# DASH_itr5_v3_labelled.net
KiCad netlist of a schematic drawn in EAGLE
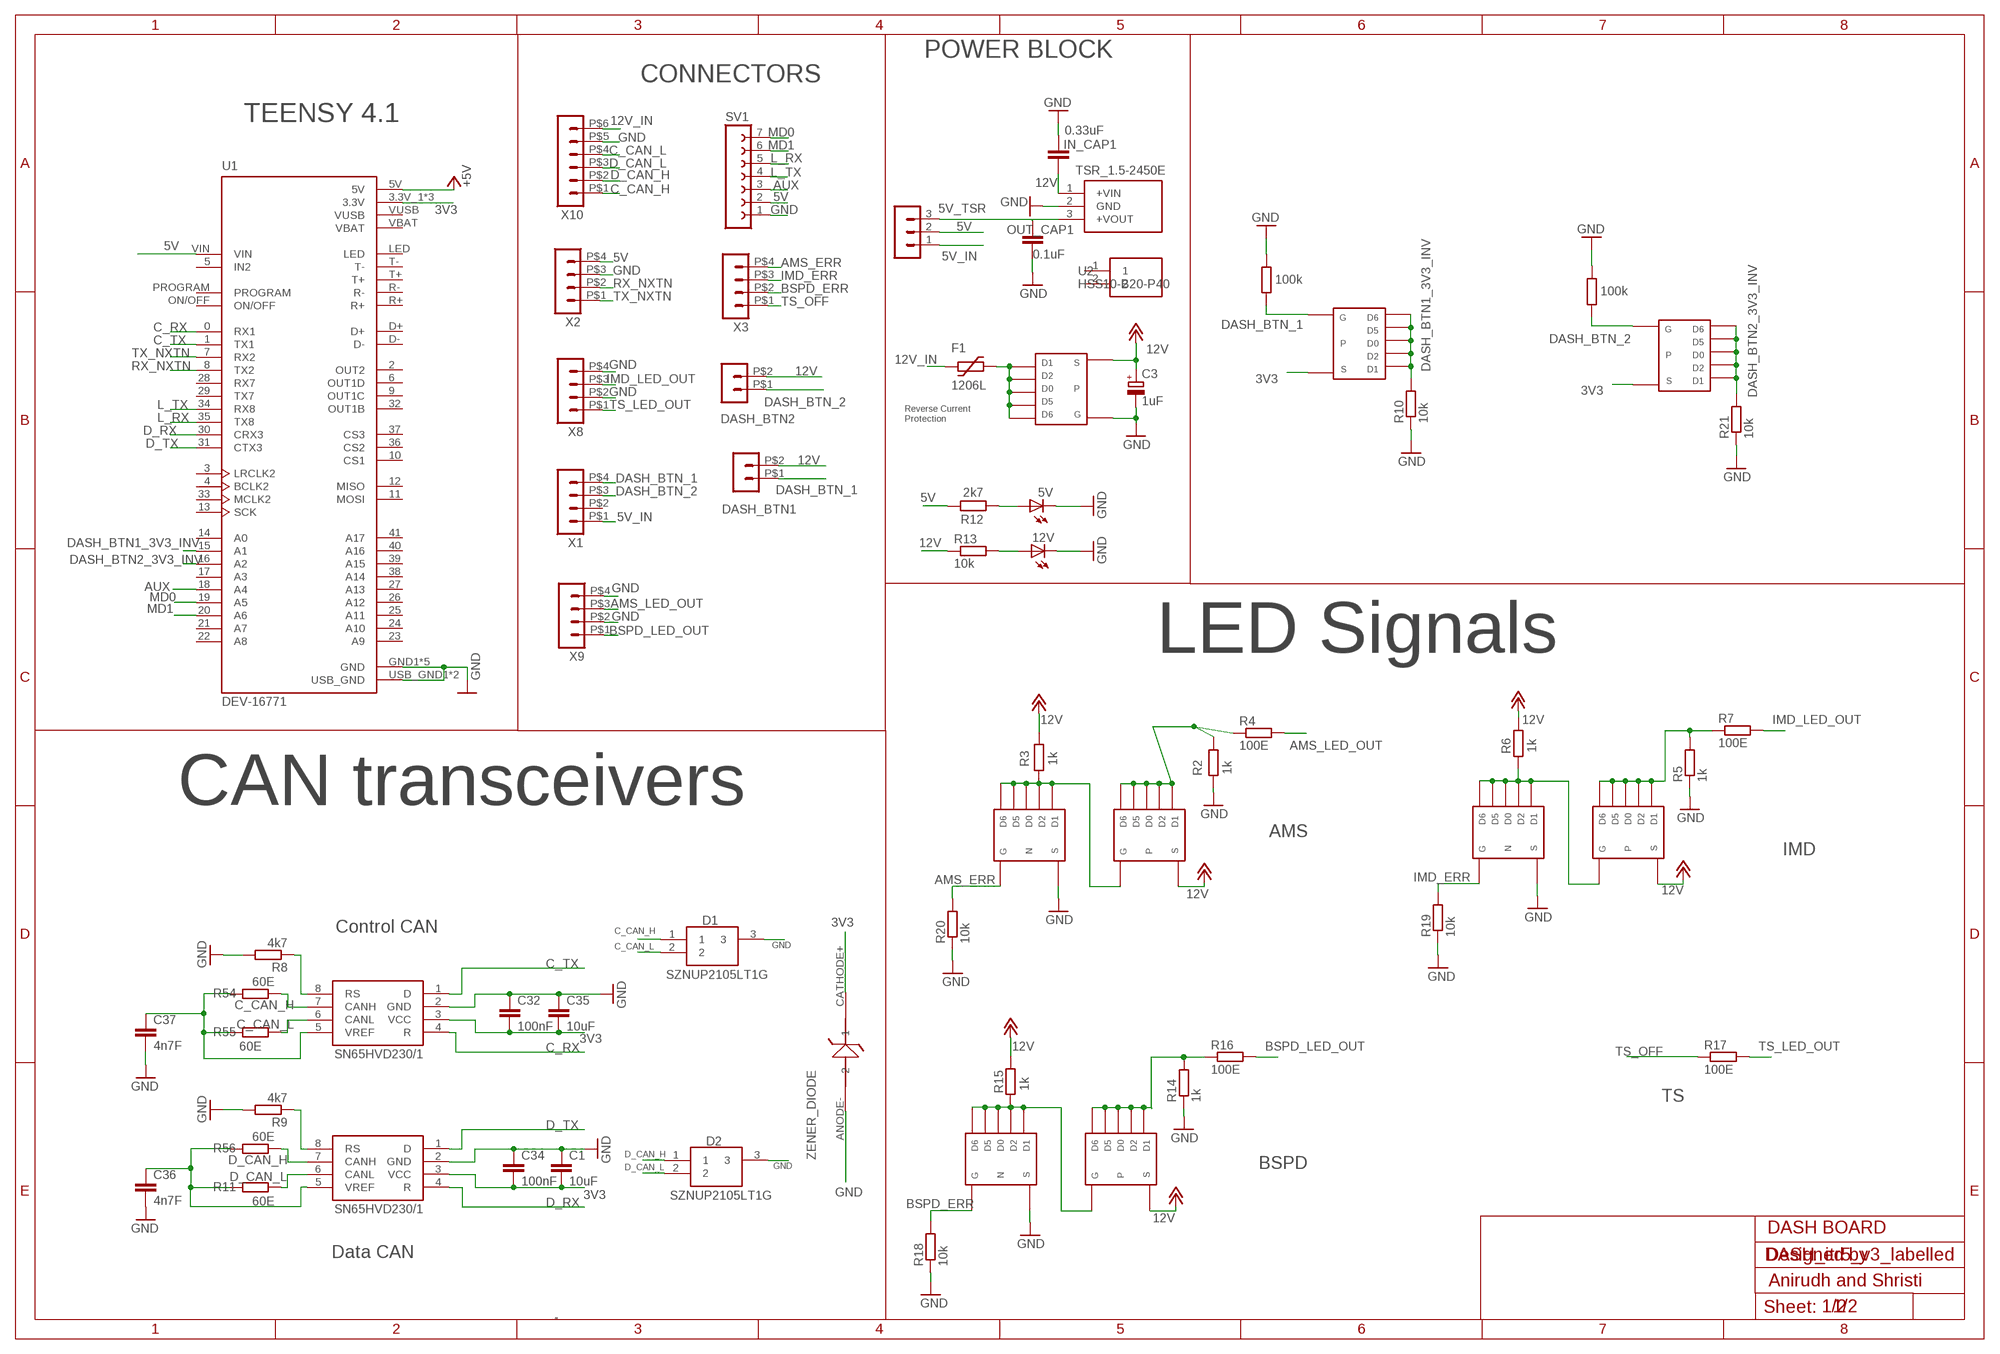
[diagram p0: schematic, sheet 1]
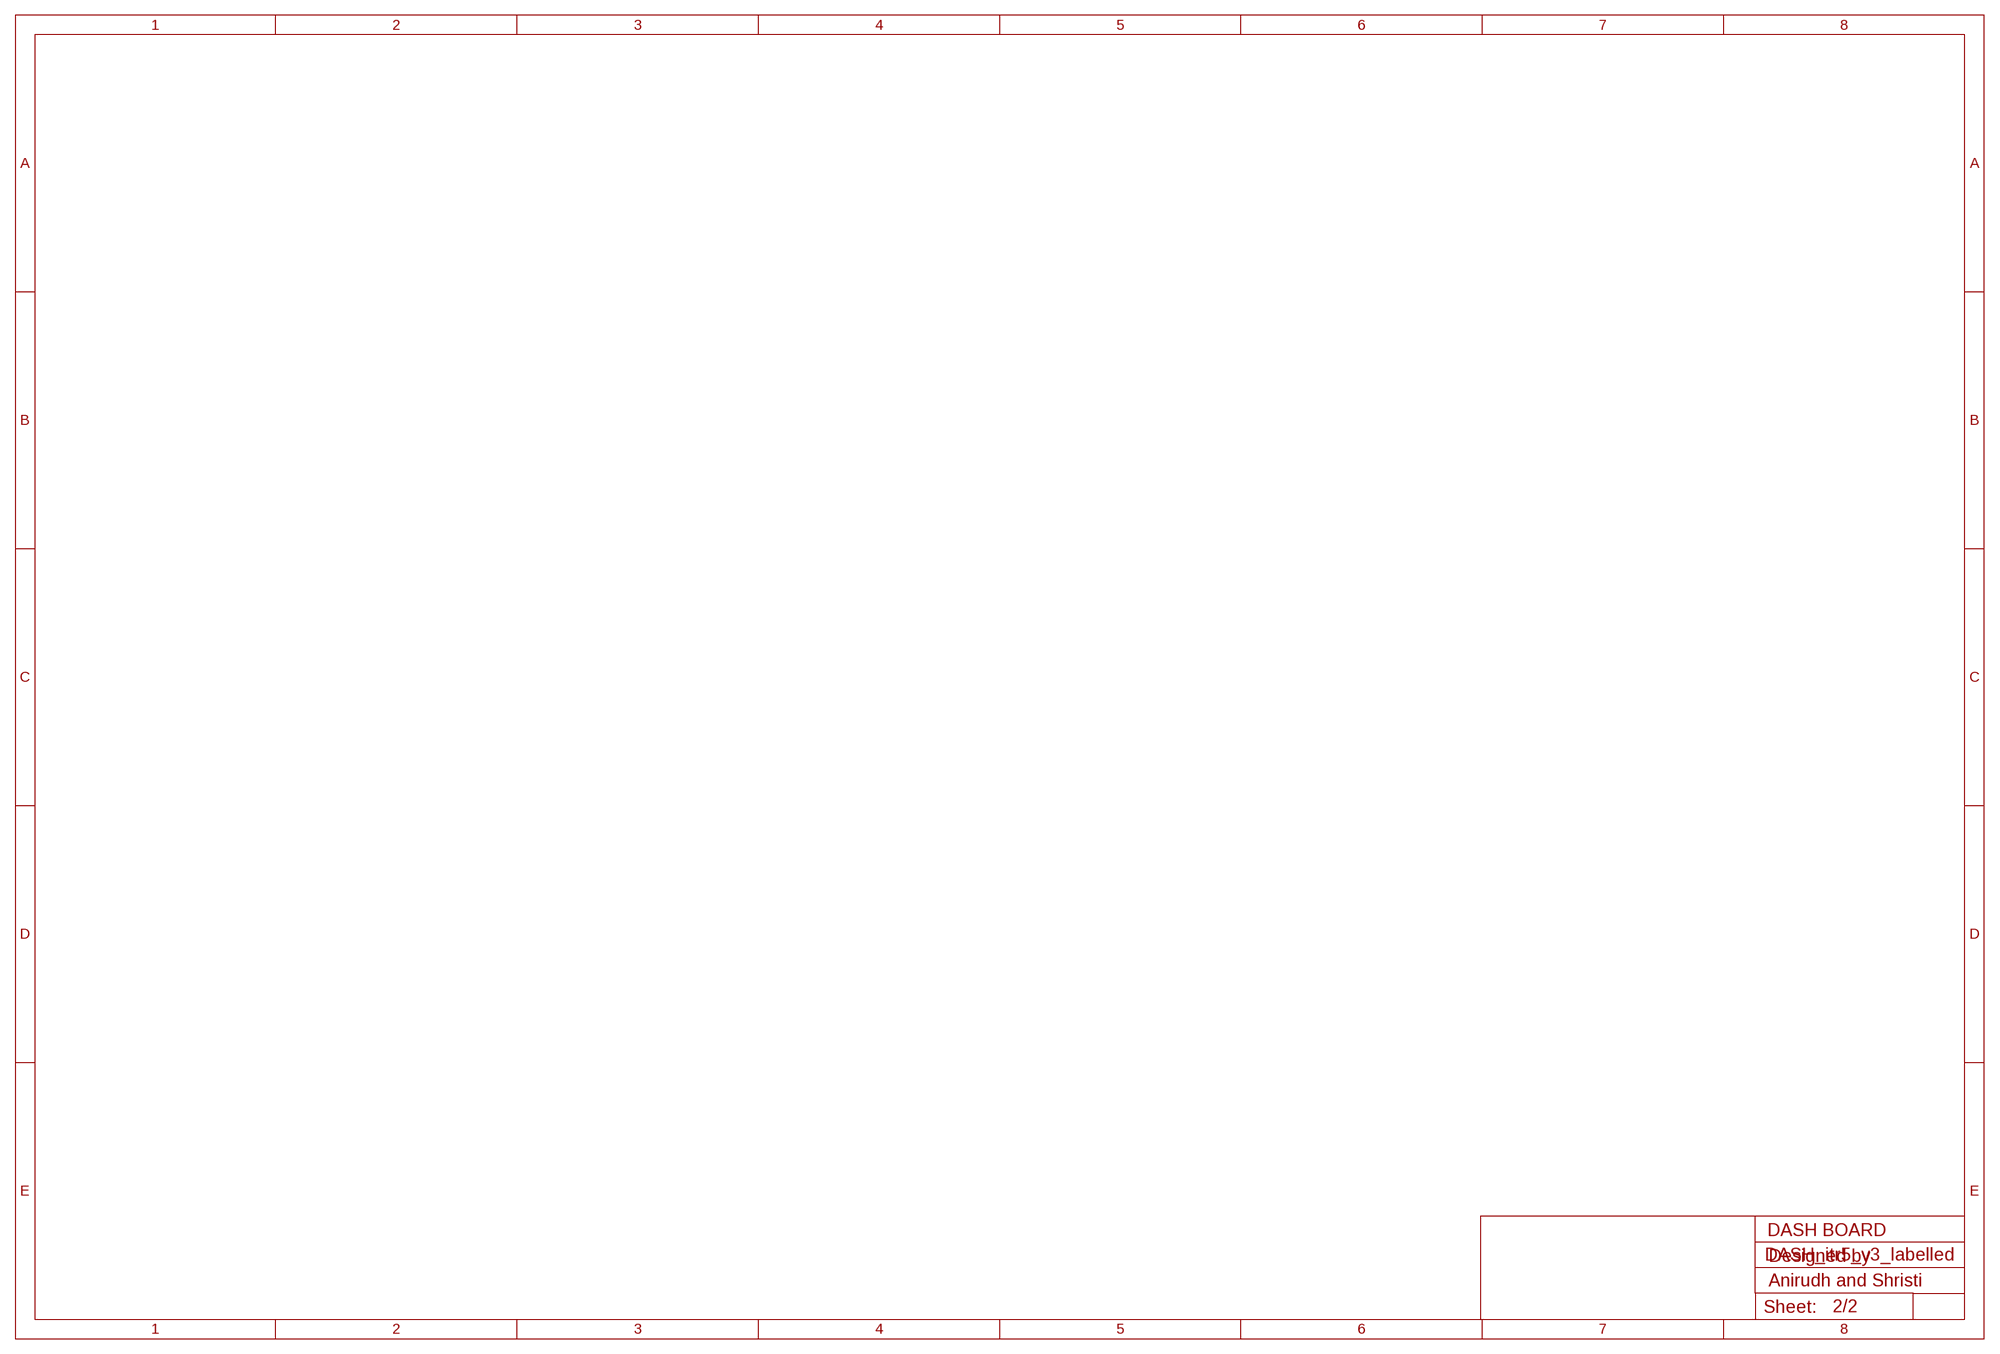
[diagram p1: schematic, sheet 2]

(export (version "E")
  (design (tool "Eeschema 10.0.6"))
  (components
    (comp (ref "5V")
      (value "LED-FKIT-1206")
      (footprint "eagle-import:FKIT-LED-1206")
      (libsource (lib "eagle-import") (part "LED-FKIT-1206"))
    )
    (comp (ref "12V")
      (value "LED-FKIT-1206")
      (footprint "eagle-import:FKIT-LED-1206")
      (libsource (lib "eagle-import") (part "LED-FKIT-1206"))
    )
    (comp (ref "C1")
      (value "10uF")
      (footprint "eagle-import:C0805")
      (libsource (lib "eagle-import") (part "C-EUC0805"))
    )
    (comp (ref "C3")
      (value "1uF")
      (footprint "eagle-import:E2,5-6")
      (libsource (lib "eagle-import") (part "CPOL-EUE2.5-6"))
    )
    (comp (ref "C32")
      (value "100nF")
      (footprint "eagle-import:C0805")
      (libsource (lib "eagle-import") (part "C-EUC0805"))
    )
    (comp (ref "C34")
      (value "100nF")
      (footprint "eagle-import:C0805")
      (libsource (lib "eagle-import") (part "C-EUC0805"))
    )
    (comp (ref "C35")
      (value "10uF")
      (footprint "eagle-import:C0805")
      (libsource (lib "eagle-import") (part "C-EUC0805"))
    )
    (comp (ref "C36")
      (value "4n7F")
      (footprint "eagle-import:C0805")
      (libsource (lib "eagle-import") (part "C-EUC0805"))
    )
    (comp (ref "C37")
      (value "4n7F")
      (footprint "eagle-import:C0805")
      (libsource (lib "eagle-import") (part "C-EUC0805"))
    )
    (comp (ref "D1")
      (value "SZNUP2105LT1G")
      (footprint "eagle-import:SOT96P237X111-3N")
      (fields (field (name "MOUSER_PART_NUMBER") "863-SZNUP2105LT1G"))
      (libsource (lib "eagle-import") (part "SZNUP2105LT1G"))
    )
    (comp (ref "D2")
      (value "SZNUP2105LT1G")
      (footprint "eagle-import:SOT96P237X111-3N")
      (fields (field (name "MOUSER_PART_NUMBER") "863-SZNUP2105LT1G"))
      (libsource (lib "eagle-import") (part "SZNUP2105LT1G"))
    )
    (comp (ref "DASH_BTN1")
      (value "HEADER_POS2_43045-0212")
      (footprint "eagle-import:43045-0212")
      (libsource (lib "eagle-import") (part "HEADER_POS2_?43045-0212"))
    )
    (comp (ref "DASH_BTN2")
      (value "HEADER_POS2_43045-0212")
      (footprint "eagle-import:43045-0212")
      (libsource (lib "eagle-import") (part "HEADER_POS2_?43045-0212"))
    )
    (comp (ref "F1")
      (value "1206L")
      (footprint "eagle-import:1206L")
      (libsource (lib "eagle-import") (part "1206L"))
    )
    (comp (ref "IN_CAP1")
      (value "0.33uF")
      (footprint "eagle-import:C0805")
      (libsource (lib "eagle-import") (part "C-EUC0805"))
    )
    (comp (ref "OUT_CAP1")
      (value "0.1uF")
      (footprint "eagle-import:C0805")
      (libsource (lib "eagle-import") (part "C-EUC0805"))
    )
    (comp (ref "PS2")
      (value "TSR_1.5-2450E")
      (footprint "eagle-import:TSR152450E")
      (fields
        (field (name "MANUFACTURER_PART_NUMBER") "TSR 1.5-2450E")
        (field (name "MOUSER_PART_NUMBER") "495-TSR1.5-2450E")
      )
      (libsource (lib "eagle-import") (part "TSR_1.5-2450E"))
    )
    (comp (ref "R1")
      (value "100k")
      (footprint "eagle-import:R0805")
      (libsource (lib "eagle-import") (part "R-EU_R0805"))
    )
    (comp (ref "R2")
      (value "1k")
      (footprint "eagle-import:R0805")
      (libsource (lib "eagle-import") (part "R-EU_R0805"))
    )
    (comp (ref "R3")
      (value "1k")
      (footprint "eagle-import:R0805")
      (libsource (lib "eagle-import") (part "R-EU_R0805"))
    )
    (comp (ref "R4")
      (value "100E")
      (footprint "eagle-import:R0805")
      (libsource (lib "eagle-import") (part "R-EU_R0805"))
    )
    (comp (ref "R5")
      (value "1k")
      (footprint "eagle-import:R0805")
      (libsource (lib "eagle-import") (part "R-EU_R0805"))
    )
    (comp (ref "R6")
      (value "1k")
      (footprint "eagle-import:R0805")
      (libsource (lib "eagle-import") (part "R-EU_R0805"))
    )
    (comp (ref "R7")
      (value "100E")
      (footprint "eagle-import:R0805")
      (libsource (lib "eagle-import") (part "R-EU_R0805"))
    )
    (comp (ref "R8")
      (value "4k7")
      (footprint "eagle-import:R0805")
      (libsource (lib "eagle-import") (part "R-EU_R0805"))
    )
    (comp (ref "R9")
      (value "4k7")
      (footprint "eagle-import:R0805")
      (libsource (lib "eagle-import") (part "R-EU_R0805"))
    )
    (comp (ref "R10")
      (value "10k")
      (footprint "eagle-import:R0805")
      (libsource (lib "eagle-import") (part "R-EU_R0805"))
    )
    (comp (ref "R11")
      (value "60E")
      (footprint "eagle-import:R0805")
      (libsource (lib "eagle-import") (part "R-EU_R0805"))
    )
    (comp (ref "R12")
      (value "2k7")
      (footprint "eagle-import:R0805")
      (libsource (lib "eagle-import") (part "R-EU_R0805"))
    )
    (comp (ref "R13")
      (value "10k")
      (footprint "eagle-import:R0805")
      (libsource (lib "eagle-import") (part "rcl_R-EU_R0805"))
    )
    (comp (ref "R14")
      (value "1k")
      (footprint "eagle-import:R0805")
      (libsource (lib "eagle-import") (part "R-EU_R0805"))
    )
    (comp (ref "R15")
      (value "1k")
      (footprint "eagle-import:R0805")
      (libsource (lib "eagle-import") (part "R-EU_R0805"))
    )
    (comp (ref "R16")
      (value "100E")
      (footprint "eagle-import:R0805")
      (libsource (lib "eagle-import") (part "R-EU_R0805"))
    )
    (comp (ref "R17")
      (value "100E")
      (footprint "eagle-import:R0805")
      (libsource (lib "eagle-import") (part "R-EU_R0805"))
    )
    (comp (ref "R18")
      (value "10k")
      (footprint "eagle-import:R0805")
      (libsource (lib "eagle-import") (part "R-EU_R0805"))
    )
    (comp (ref "R19")
      (value "10k")
      (footprint "eagle-import:R0805")
      (libsource (lib "eagle-import") (part "R-EU_R0805"))
    )
    (comp (ref "R20")
      (value "10k")
      (footprint "eagle-import:R0805")
      (libsource (lib "eagle-import") (part "R-EU_R0805"))
    )
    (comp (ref "R21")
      (value "10k")
      (footprint "eagle-import:R0805")
      (libsource (lib "eagle-import") (part "R-EU_R0805"))
    )
    (comp (ref "R35")
      (value "100k")
      (footprint "eagle-import:R0805")
      (libsource (lib "eagle-import") (part "R-EU_R0805"))
    )
    (comp (ref "R54")
      (value "60E")
      (footprint "eagle-import:R0805")
      (libsource (lib "eagle-import") (part "R-EU_R0805"))
    )
    (comp (ref "R55")
      (value "60E")
      (footprint "eagle-import:R0805")
      (libsource (lib "eagle-import") (part "R-EU_R0805"))
    )
    (comp (ref "R56")
      (value "60E")
      (footprint "eagle-import:R0805")
      (libsource (lib "eagle-import") (part "R-EU_R0805"))
    )
    (comp (ref "SV1")
      (value "FE07-1")
      (footprint "eagle-import:FE07")
      (libsource (lib "eagle-import") (part "FE07-1"))
    )
    (comp (ref "SV3")
      (value "MA03-1")
      (footprint "eagle-import:MA03-1")
      (libsource (lib "eagle-import") (part "MA03-1"))
    )
    (comp (ref "U$1")
      (value "SN65HVD230/1")
      (footprint "eagle-import:SO8")
      (libsource (lib "eagle-import") (part "SN65HVD230/1"))
    )
    (comp (ref "U$3")
      (value "SN65HVD230/1")
      (footprint "eagle-import:SO8")
      (libsource (lib "eagle-import") (part "SN65HVD230/1"))
    )
    (comp (ref "U$4")
      (value "TSOP-6_NMOS")
      (footprint "eagle-import:TSOP-6_NMOS")
      (libsource (lib "eagle-import") (part "TSOP-6_NMOS"))
    )
    (comp (ref "U$5")
      (value "TSOP-6_PMOS")
      (footprint "eagle-import:TSOP-6_PMOS")
      (libsource (lib "eagle-import") (part "TSOP-6_PMOS"))
    )
    (comp (ref "U$6")
      (value "TSOP-6_NMOS")
      (footprint "eagle-import:TSOP-6_NMOS")
      (libsource (lib "eagle-import") (part "TSOP-6_NMOS"))
    )
    (comp (ref "U$9")
      (value "TSOP-6_PMOS")
      (footprint "eagle-import:TSOP-6_PMOS")
      (libsource (lib "eagle-import") (part "TSOP-6_PMOS"))
    )
    (comp (ref "U$10")
      (value "TSOP-6_PMOS")
      (footprint "eagle-import:TSOP-6_PMOS")
      (libsource (lib "eagle-import") (part "TSOP-6_PMOS"))
    )
    (comp (ref "U$11")
      (value "TSOP-6_NMOS")
      (footprint "eagle-import:TSOP-6_NMOS")
      (libsource (lib "eagle-import") (part "TSOP-6_NMOS"))
    )
    (comp (ref "U$12")
      (value "TSOP-6_PMOS")
      (footprint "eagle-import:TSOP-6_PMOS")
      (libsource (lib "eagle-import") (part "TSOP-6_PMOS"))
    )
    (comp (ref "U$13")
      (value "TSOP-6_PMOS")
      (footprint "eagle-import:TSOP-6_PMOS")
      (libsource (lib "eagle-import") (part "TSOP-6_PMOS"))
    )
    (comp (ref "U$14")
      (value "TSOP-6_PMOS")
      (footprint "eagle-import:TSOP-6_PMOS")
      (libsource (lib "eagle-import") (part "TSOP-6_PMOS"))
    )
    (comp (ref "U$20")
      (value "ZENER_DIODE")
      (footprint "eagle-import:SOD323HE")
      (libsource (lib "eagle-import") (part "ZENER_DIODE"))
    )
    (comp (ref "U1")
      (value "DEV-16771")
      (footprint "eagle-import:MODULE_DEV-16771")
      (fields (field (name "MF") "SparkFun Electronics"))
      (libsource (lib "eagle-import") (part "DEV-16771"))
    )
    (comp (ref "U2")
      (value "HSS10-B20-P40")
      (footprint "eagle-import:HSS10B20P40")
      (fields (field (name "MOUSER_PART_NUMBER") "490-HSS10-B20-P40"))
      (libsource (lib "eagle-import") (part "HSS10-B20-P40"))
    )
    (comp (ref "X1")
      (value "HEADER_POS4_43045-0412")
      (footprint "eagle-import:43045-0412")
      (libsource (lib "eagle-import") (part "HEADER_POS4_?43045-0412"))
    )
    (comp (ref "X2")
      (value "HEADER_POS4_43045-0412")
      (footprint "eagle-import:43045-0412")
      (libsource (lib "eagle-import") (part "HEADER_POS4_?43045-0412"))
    )
    (comp (ref "X3")
      (value "HEADER_POS4_43045-0412")
      (footprint "eagle-import:43045-0412")
      (libsource (lib "eagle-import") (part "HEADER_POS4_?43045-0412"))
    )
    (comp (ref "X8")
      (value "HEADER_POS4_43045-0412")
      (footprint "eagle-import:43045-0412")
      (libsource (lib "eagle-import") (part "HEADER_POS4_?43045-0412"))
    )
    (comp (ref "X9")
      (value "HEADER_POS4_43045-0412")
      (footprint "eagle-import:43045-0412")
      (libsource (lib "eagle-import") (part "HEADER_POS4_?43045-0412"))
    )
    (comp (ref "X10")
      (value "HEADER_POS6_43045-0612")
      (footprint "eagle-import:43045-0612")
      (libsource (lib "eagle-import") (part "HEADER_POS6_?43045-0612"))
    )
  )
  (nets
    (net (code "1") (name "+5V") (class "Default")
      (node (ref "U1") (pin "5V") (pinfunction "5V_5V") (pintype "power_in"))
    )
    (net (code "2") (name "3V3") (class "Default")
      (node (ref "C1") (pin "2") (pinfunction "2_2") (pintype "passive"))
      (node (ref "C32") (pin "2") (pinfunction "2_2") (pintype "passive"))
      (node (ref "C34") (pin "2") (pinfunction "2_2") (pintype "passive"))
      (node (ref "C35") (pin "2") (pinfunction "2_2") (pintype "passive"))
      (node (ref "U$1") (pin "3") (pinfunction "VCC_3") (pintype "power_in"))
      (node (ref "U$10") (pin "S") (pinfunction "S_S") (pintype "bidirectional"))
      (node (ref "U$12") (pin "S") (pinfunction "S_S") (pintype "bidirectional"))
      (node (ref "U$20") (pin "CATHODE+") (pinfunction "1_CATHODE+") (pintype "bidirectional"))
      (node (ref "U$3") (pin "3") (pinfunction "VCC_3") (pintype "power_in"))
      (node (ref "U1") (pin "3.3V_1") (pinfunction "3.3V_3.3V_1") (pintype "power_in"))
      (node (ref "U1") (pin "3.3V_2") (pinfunction "3.3V_3.3V_2") (pintype "power_in"))
      (node (ref "U1") (pin "3.3V_3") (pinfunction "3.3V_3.3V_3") (pintype "power_in"))
    )
    (net (code "3") (name "5V") (class "Default")
      (node (ref "R12") (pin "2") (pinfunction "2_2") (pintype "passive"))
      (node (ref "SV1") (pin "2") (pinfunction "2_2") (pintype "passive"))
      (node (ref "SV3") (pin "2") (pinfunction "2_2") (pintype "passive"))
      (node (ref "U1") (pin "VIN") (pinfunction "VIN_VIN") (pintype "input"))
      (node (ref "X2") (pin "P$4") (pinfunction "4_P$4") (pintype "passive"))
    )
    (net (code "4") (name "5V_IN") (class "Default")
      (node (ref "SV3") (pin "1") (pinfunction "1_1") (pintype "passive"))
      (node (ref "X1") (pin "P$1") (pinfunction "1_P$1") (pintype "passive"))
    )
    (net (code "5") (name "5V_TSR") (class "Default")
      (node (ref "OUT_CAP1") (pin "1") (pinfunction "1_1") (pintype "passive"))
      (node (ref "PS2") (pin "3") (pinfunction "+VOUT_3") (pintype "bidirectional"))
      (node (ref "SV3") (pin "3") (pinfunction "3_3") (pintype "passive"))
    )
    (net (code "6") (name "12V") (class "Default")
      (node (ref "C3") (pin "+") (pinfunction "+_+") (pintype "passive"))
      (node (ref "DASH_BTN1") (pin "P$2") (pinfunction "2_P$2") (pintype "passive"))
      (node (ref "DASH_BTN2") (pin "P$2") (pinfunction "2_P$2") (pintype "passive"))
      (node (ref "IN_CAP1") (pin "1") (pinfunction "1_1") (pintype "passive"))
      (node (ref "PS2") (pin "1") (pinfunction "+VIN_1") (pintype "bidirectional"))
      (node (ref "R13") (pin "1") (pinfunction "1_1") (pintype "passive"))
      (node (ref "R15") (pin "2") (pinfunction "2_2") (pintype "passive"))
      (node (ref "R3") (pin "2") (pinfunction "2_2") (pintype "passive"))
      (node (ref "R6") (pin "2") (pinfunction "2_2") (pintype "passive"))
      (node (ref "U$13") (pin "S") (pinfunction "S_S") (pintype "bidirectional"))
      (node (ref "U$14") (pin "S") (pinfunction "S_S") (pintype "bidirectional"))
      (node (ref "U$5") (pin "S") (pinfunction "S_S") (pintype "bidirectional"))
      (node (ref "U$9") (pin "S") (pinfunction "S_S") (pintype "bidirectional"))
    )
    (net (code "7") (name "12V_IN") (class "Default")
      (node (ref "F1") (pin "P$1") (pinfunction "1_P$1") (pintype "passive"))
      (node (ref "X10") (pin "P$6") (pinfunction "6_P$6") (pintype "passive"))
    )
    (net (code "8") (name "AMS_ERR") (class "Default")
      (node (ref "R20") (pin "2") (pinfunction "2_2") (pintype "passive"))
      (node (ref "U$4") (pin "G") (pinfunction "G_G") (pintype "bidirectional"))
      (node (ref "X3") (pin "P$4") (pinfunction "4_P$4") (pintype "passive"))
    )
    (net (code "9") (name "AMS_LED_OUT") (class "Default")
      (node (ref "R4") (pin "2") (pinfunction "2_2") (pintype "passive"))
      (node (ref "X9") (pin "P$3") (pinfunction "3_P$3") (pintype "passive"))
    )
    (net (code "10") (name "AUX") (class "Default")
      (node (ref "SV1") (pin "3") (pinfunction "3_3") (pintype "passive"))
      (node (ref "U1") (pin "18") (pinfunction "A4_18") (pintype "bidirectional"))
    )
    (net (code "11") (name "BSPD_ERR") (class "Default")
      (node (ref "R18") (pin "2") (pinfunction "2_2") (pintype "passive"))
      (node (ref "U$11") (pin "G") (pinfunction "G_G") (pintype "bidirectional"))
      (node (ref "X3") (pin "P$2") (pinfunction "2_P$2") (pintype "passive"))
    )
    (net (code "12") (name "BSPD_LED_OUT") (class "Default")
      (node (ref "R16") (pin "2") (pinfunction "2_2") (pintype "passive"))
      (node (ref "X9") (pin "P$1") (pinfunction "1_P$1") (pintype "passive"))
    )
    (net (code "13") (name "C_CAN_H") (class "Default")
      (node (ref "D1") (pin "1") (pinfunction "1_1") (pintype "bidirectional"))
      (node (ref "R54") (pin "1") (pinfunction "1_1") (pintype "passive"))
      (node (ref "U$3") (pin "7") (pinfunction "CANH_7") (pintype "bidirectional"))
      (node (ref "X10") (pin "P$1") (pinfunction "1_P$1") (pintype "passive"))
    )
    (net (code "14") (name "C_CAN_L") (class "Default")
      (node (ref "D1") (pin "2") (pinfunction "2_2") (pintype "bidirectional"))
      (node (ref "R55") (pin "1") (pinfunction "1_1") (pintype "passive"))
      (node (ref "U$3") (pin "6") (pinfunction "CANL_6") (pintype "bidirectional"))
      (node (ref "X10") (pin "P$4") (pinfunction "4_P$4") (pintype "passive"))
    )
    (net (code "15") (name "C_RX") (class "Default")
      (node (ref "U$3") (pin "4") (pinfunction "R_4") (pintype "bidirectional"))
      (node (ref "U1") (pin "0") (pinfunction "RX1_0") (pintype "bidirectional"))
    )
    (net (code "16") (name "C_TX") (class "Default")
      (node (ref "U$3") (pin "1") (pinfunction "D_1") (pintype "bidirectional"))
      (node (ref "U1") (pin "1") (pinfunction "TX1_1") (pintype "bidirectional"))
    )
    (net (code "17") (name "DASH_BTN1_3V3_INV") (class "Default")
      (node (ref "R10") (pin "2") (pinfunction "2_2") (pintype "passive"))
      (node (ref "U$10") (pin "1") (pinfunction "1_1") (pintype "bidirectional"))
      (node (ref "U$10") (pin "2") (pinfunction "2_2") (pintype "bidirectional"))
      (node (ref "U$10") (pin "5") (pinfunction "5_5") (pintype "bidirectional"))
      (node (ref "U$10") (pin "6") (pinfunction "6_6") (pintype "bidirectional"))
      (node (ref "U$10") (pin "D") (pinfunction "D0_D") (pintype "bidirectional"))
      (node (ref "U1") (pin "15") (pinfunction "A1_15") (pintype "bidirectional"))
    )
    (net (code "18") (name "DASH_BTN2_3V3_INV") (class "Default")
      (node (ref "R21") (pin "2") (pinfunction "2_2") (pintype "passive"))
      (node (ref "U$12") (pin "1") (pinfunction "1_1") (pintype "bidirectional"))
      (node (ref "U$12") (pin "2") (pinfunction "2_2") (pintype "bidirectional"))
      (node (ref "U$12") (pin "5") (pinfunction "5_5") (pintype "bidirectional"))
      (node (ref "U$12") (pin "6") (pinfunction "6_6") (pintype "bidirectional"))
      (node (ref "U$12") (pin "D") (pinfunction "D0_D") (pintype "bidirectional"))
      (node (ref "U1") (pin "16") (pinfunction "A2_16") (pintype "bidirectional"))
    )
    (net (code "19") (name "DASH_BTN_1") (class "Default")
      (node (ref "DASH_BTN1") (pin "P$1") (pinfunction "1_P$1") (pintype "passive"))
      (node (ref "R35") (pin "1") (pinfunction "1_1") (pintype "passive"))
      (node (ref "U$10") (pin "G") (pinfunction "G_G") (pintype "bidirectional"))
      (node (ref "X1") (pin "P$4") (pinfunction "4_P$4") (pintype "passive"))
    )
    (net (code "20") (name "DASH_BTN_2") (class "Default")
      (node (ref "DASH_BTN2") (pin "P$1") (pinfunction "1_P$1") (pintype "passive"))
      (node (ref "R1") (pin "1") (pinfunction "1_1") (pintype "passive"))
      (node (ref "U$12") (pin "G") (pinfunction "G_G") (pintype "bidirectional"))
      (node (ref "X1") (pin "P$3") (pinfunction "3_P$3") (pintype "passive"))
    )
    (net (code "21") (name "D_CAN_H") (class "Default")
      (node (ref "D2") (pin "1") (pinfunction "1_1") (pintype "bidirectional"))
      (node (ref "R56") (pin "1") (pinfunction "1_1") (pintype "passive"))
      (node (ref "U$1") (pin "7") (pinfunction "CANH_7") (pintype "bidirectional"))
      (node (ref "X10") (pin "P$2") (pinfunction "2_P$2") (pintype "passive"))
    )
    (net (code "22") (name "D_CAN_L") (class "Default")
      (node (ref "D2") (pin "2") (pinfunction "2_2") (pintype "bidirectional"))
      (node (ref "R11") (pin "1") (pinfunction "1_1") (pintype "passive"))
      (node (ref "U$1") (pin "6") (pinfunction "CANL_6") (pintype "bidirectional"))
      (node (ref "X10") (pin "P$3") (pinfunction "3_P$3") (pintype "passive"))
    )
    (net (code "23") (name "D_RX") (class "Default")
      (node (ref "U$1") (pin "4") (pinfunction "R_4") (pintype "bidirectional"))
      (node (ref "U1") (pin "30") (pinfunction "CRX3_30") (pintype "bidirectional"))
    )
    (net (code "24") (name "D_TX") (class "Default")
      (node (ref "U$1") (pin "1") (pinfunction "D_1") (pintype "bidirectional"))
      (node (ref "U1") (pin "31") (pinfunction "CTX3_31") (pintype "bidirectional"))
    )
    (net (code "25") (name "GND") (class "Default")
      (node (ref "12V") (pin "C") (pinfunction "C_C") (pintype "passive"))
      (node (ref "5V") (pin "C") (pinfunction "C_C") (pintype "passive"))
      (node (ref "C1") (pin "1") (pinfunction "1_1") (pintype "passive"))
      (node (ref "C3") (pin "-") (pinfunction "-_-") (pintype "passive"))
      (node (ref "C32") (pin "1") (pinfunction "1_1") (pintype "passive"))
      (node (ref "C34") (pin "1") (pinfunction "1_1") (pintype "passive"))
      (node (ref "C35") (pin "1") (pinfunction "1_1") (pintype "passive"))
      (node (ref "C36") (pin "2") (pinfunction "2_2") (pintype "passive"))
      (node (ref "C37") (pin "2") (pinfunction "2_2") (pintype "passive"))
      (node (ref "D1") (pin "3") (pinfunction "3_3") (pintype "bidirectional"))
      (node (ref "D2") (pin "3") (pinfunction "3_3") (pintype "bidirectional"))
      (node (ref "IN_CAP1") (pin "2") (pinfunction "2_2") (pintype "passive"))
      (node (ref "OUT_CAP1") (pin "2") (pinfunction "2_2") (pintype "passive"))
      (node (ref "PS2") (pin "2") (pinfunction "GND_2") (pintype "bidirectional"))
      (node (ref "R1") (pin "2") (pinfunction "2_2") (pintype "passive"))
      (node (ref "R10") (pin "1") (pinfunction "1_1") (pintype "passive"))
      (node (ref "R14") (pin "1") (pinfunction "1_1") (pintype "passive"))
      (node (ref "R18") (pin "1") (pinfunction "1_1") (pintype "passive"))
      (node (ref "R19") (pin "1") (pinfunction "1_1") (pintype "passive"))
      (node (ref "R2") (pin "1") (pinfunction "1_1") (pintype "passive"))
      (node (ref "R20") (pin "1") (pinfunction "1_1") (pintype "passive"))
      (node (ref "R21") (pin "1") (pinfunction "1_1") (pintype "passive"))
      (node (ref "R35") (pin "2") (pinfunction "2_2") (pintype "passive"))
      (node (ref "R5") (pin "1") (pinfunction "1_1") (pintype "passive"))
      (node (ref "R8") (pin "2") (pinfunction "2_2") (pintype "passive"))
      (node (ref "R9") (pin "2") (pinfunction "2_2") (pintype "passive"))
      (node (ref "SV1") (pin "1") (pinfunction "1_1") (pintype "passive"))
      (node (ref "U$1") (pin "2") (pinfunction "GND_2") (pintype "power_in"))
      (node (ref "U$11") (pin "S") (pinfunction "S_S") (pintype "bidirectional"))
      (node (ref "U$13") (pin "G") (pinfunction "G_G") (pintype "bidirectional"))
      (node (ref "U$20") (pin "ANODE-") (pinfunction "2_ANODE-") (pintype "bidirectional"))
      (node (ref "U$3") (pin "2") (pinfunction "GND_2") (pintype "power_in"))
      (node (ref "U$4") (pin "S") (pinfunction "S_S") (pintype "bidirectional"))
      (node (ref "U$6") (pin "S") (pinfunction "S_S") (pintype "bidirectional"))
      (node (ref "U1") (pin "GND1") (pinfunction "GND_GND1") (pintype "power_in"))
      (node (ref "U1") (pin "GND2") (pinfunction "GND_GND2") (pintype "power_in"))
      (node (ref "U1") (pin "GND3") (pinfunction "GND_GND3") (pintype "power_in"))
      (node (ref "U1") (pin "GND4") (pinfunction "GND_GND4") (pintype "power_in"))
      (node (ref "U1") (pin "GND5") (pinfunction "GND_GND5") (pintype "power_in"))
      (node (ref "U1") (pin "USB_GND1") (pinfunction "USB_GND_USB_GND1") (pintype "power_in"))
      (node (ref "U1") (pin "USB_GND2") (pinfunction "USB_GND_USB_GND2") (pintype "power_in"))
      (node (ref "X10") (pin "P$5") (pinfunction "5_P$5") (pintype "passive"))
      (node (ref "X2") (pin "P$3") (pinfunction "3_P$3") (pintype "passive"))
      (node (ref "X8") (pin "P$2") (pinfunction "2_P$2") (pintype "passive"))
      (node (ref "X8") (pin "P$4") (pinfunction "4_P$4") (pintype "passive"))
      (node (ref "X9") (pin "P$2") (pinfunction "2_P$2") (pintype "passive"))
      (node (ref "X9") (pin "P$4") (pinfunction "4_P$4") (pintype "passive"))
    )
    (net (code "26") (name "IMD_ERR") (class "Default")
      (node (ref "R19") (pin "2") (pinfunction "2_2") (pintype "passive"))
      (node (ref "U$6") (pin "G") (pinfunction "G_G") (pintype "bidirectional"))
      (node (ref "X3") (pin "P$3") (pinfunction "3_P$3") (pintype "passive"))
    )
    (net (code "27") (name "IMD_LED_OUT") (class "Default")
      (node (ref "R7") (pin "2") (pinfunction "2_2") (pintype "passive"))
      (node (ref "X8") (pin "P$3") (pinfunction "3_P$3") (pintype "passive"))
    )
    (net (code "28") (name "L_RX") (class "Default")
      (node (ref "SV1") (pin "5") (pinfunction "5_5") (pintype "passive"))
      (node (ref "U1") (pin "35") (pinfunction "TX8_35") (pintype "bidirectional"))
    )
    (net (code "29") (name "L_TX") (class "Default")
      (node (ref "SV1") (pin "4") (pinfunction "4_4") (pintype "passive"))
      (node (ref "U1") (pin "34") (pinfunction "RX8_34") (pintype "bidirectional"))
    )
    (net (code "30") (name "MD0") (class "Default")
      (node (ref "SV1") (pin "7") (pinfunction "7_7") (pintype "passive"))
      (node (ref "U1") (pin "19") (pinfunction "A5_19") (pintype "bidirectional"))
    )
    (net (code "31") (name "MD1") (class "Default")
      (node (ref "SV1") (pin "6") (pinfunction "6_6") (pintype "passive"))
      (node (ref "U1") (pin "20") (pinfunction "A6_20") (pintype "bidirectional"))
    )
    (net (code "32") (name "Net-(5V-PadA)") (class "Default")
      (node (ref "5V") (pin "A") (pinfunction "A_A") (pintype "passive"))
      (node (ref "R12") (pin "1") (pinfunction "1_1") (pintype "passive"))
    )
    (net (code "33") (name "Net-(12V-PadA)") (class "Default")
      (node (ref "12V") (pin "A") (pinfunction "A_A") (pintype "passive"))
      (node (ref "R13") (pin "2") (pinfunction "2_2") (pintype "passive"))
    )
    (net (code "34") (name "Net-(F1-2)") (class "Default")
      (node (ref "F1") (pin "P$2") (pinfunction "2_P$2") (pintype "passive"))
      (node (ref "U$13") (pin "1") (pinfunction "1_1") (pintype "bidirectional"))
      (node (ref "U$13") (pin "2") (pinfunction "2_2") (pintype "bidirectional"))
      (node (ref "U$13") (pin "5") (pinfunction "5_5") (pintype "bidirectional"))
      (node (ref "U$13") (pin "6") (pinfunction "6_6") (pintype "bidirectional"))
      (node (ref "U$13") (pin "D") (pinfunction "D0_D") (pintype "bidirectional"))
    )
    (net (code "35") (name "Net-(U$1-RS)") (class "Default")
      (node (ref "R9") (pin "1") (pinfunction "1_1") (pintype "passive"))
      (node (ref "U$1") (pin "8") (pinfunction "RS_8") (pintype "bidirectional"))
    )
    (net (code "36") (name "Net-(U$1-VREF)") (class "Default")
      (node (ref "C36") (pin "1") (pinfunction "1_1") (pintype "passive"))
      (node (ref "R11") (pin "2") (pinfunction "2_2") (pintype "passive"))
      (node (ref "R56") (pin "2") (pinfunction "2_2") (pintype "passive"))
      (node (ref "U$1") (pin "5") (pinfunction "VREF_5") (pintype "bidirectional"))
    )
    (net (code "37") (name "Net-(U$3-RS)") (class "Default")
      (node (ref "R8") (pin "1") (pinfunction "1_1") (pintype "passive"))
      (node (ref "U$3") (pin "8") (pinfunction "RS_8") (pintype "bidirectional"))
    )
    (net (code "38") (name "Net-(U$3-VREF)") (class "Default")
      (node (ref "C37") (pin "1") (pinfunction "1_1") (pintype "passive"))
      (node (ref "R54") (pin "2") (pinfunction "2_2") (pintype "passive"))
      (node (ref "R55") (pin "2") (pinfunction "2_2") (pintype "passive"))
      (node (ref "U$3") (pin "5") (pinfunction "VREF_5") (pintype "bidirectional"))
    )
    (net (code "39") (name "Net-(U$4-D0)") (class "Default")
      (node (ref "R3") (pin "1") (pinfunction "1_1") (pintype "passive"))
      (node (ref "U$4") (pin "1") (pinfunction "1_1") (pintype "bidirectional"))
      (node (ref "U$4") (pin "2") (pinfunction "2_2") (pintype "bidirectional"))
      (node (ref "U$4") (pin "5") (pinfunction "5_5") (pintype "bidirectional"))
      (node (ref "U$4") (pin "6") (pinfunction "6_6") (pintype "bidirectional"))
      (node (ref "U$4") (pin "D") (pinfunction "D0_D") (pintype "bidirectional"))
      (node (ref "U$5") (pin "G") (pinfunction "G_G") (pintype "bidirectional"))
    )
    (net (code "40") (name "Net-(U$5-D0)") (class "Default")
      (node (ref "R2") (pin "2") (pinfunction "2_2") (pintype "passive"))
      (node (ref "R4") (pin "1") (pinfunction "1_1") (pintype "passive"))
      (node (ref "U$5") (pin "1") (pinfunction "1_1") (pintype "bidirectional"))
      (node (ref "U$5") (pin "2") (pinfunction "2_2") (pintype "bidirectional"))
      (node (ref "U$5") (pin "5") (pinfunction "5_5") (pintype "bidirectional"))
      (node (ref "U$5") (pin "6") (pinfunction "6_6") (pintype "bidirectional"))
      (node (ref "U$5") (pin "D") (pinfunction "D0_D") (pintype "bidirectional"))
    )
    (net (code "41") (name "Net-(U$6-D0)") (class "Default")
      (node (ref "R6") (pin "1") (pinfunction "1_1") (pintype "passive"))
      (node (ref "U$6") (pin "1") (pinfunction "1_1") (pintype "bidirectional"))
      (node (ref "U$6") (pin "2") (pinfunction "2_2") (pintype "bidirectional"))
      (node (ref "U$6") (pin "5") (pinfunction "5_5") (pintype "bidirectional"))
      (node (ref "U$6") (pin "6") (pinfunction "6_6") (pintype "bidirectional"))
      (node (ref "U$6") (pin "D") (pinfunction "D0_D") (pintype "bidirectional"))
      (node (ref "U$9") (pin "G") (pinfunction "G_G") (pintype "bidirectional"))
    )
    (net (code "42") (name "Net-(U$9-D0)") (class "Default")
      (node (ref "R5") (pin "2") (pinfunction "2_2") (pintype "passive"))
      (node (ref "R7") (pin "1") (pinfunction "1_1") (pintype "passive"))
      (node (ref "U$9") (pin "1") (pinfunction "1_1") (pintype "bidirectional"))
      (node (ref "U$9") (pin "2") (pinfunction "2_2") (pintype "bidirectional"))
      (node (ref "U$9") (pin "5") (pinfunction "5_5") (pintype "bidirectional"))
      (node (ref "U$9") (pin "6") (pinfunction "6_6") (pintype "bidirectional"))
      (node (ref "U$9") (pin "D") (pinfunction "D0_D") (pintype "bidirectional"))
    )
    (net (code "43") (name "Net-(U$11-D0)") (class "Default")
      (node (ref "R15") (pin "1") (pinfunction "1_1") (pintype "passive"))
      (node (ref "U$11") (pin "1") (pinfunction "1_1") (pintype "bidirectional"))
      (node (ref "U$11") (pin "2") (pinfunction "2_2") (pintype "bidirectional"))
      (node (ref "U$11") (pin "5") (pinfunction "5_5") (pintype "bidirectional"))
      (node (ref "U$11") (pin "6") (pinfunction "6_6") (pintype "bidirectional"))
      (node (ref "U$11") (pin "D") (pinfunction "D0_D") (pintype "bidirectional"))
      (node (ref "U$14") (pin "G") (pinfunction "G_G") (pintype "bidirectional"))
    )
    (net (code "44") (name "Net-(U$14-D0)") (class "Default")
      (node (ref "R14") (pin "2") (pinfunction "2_2") (pintype "passive"))
      (node (ref "R16") (pin "1") (pinfunction "1_1") (pintype "passive"))
      (node (ref "U$14") (pin "1") (pinfunction "1_1") (pintype "bidirectional"))
      (node (ref "U$14") (pin "2") (pinfunction "2_2") (pintype "bidirectional"))
      (node (ref "U$14") (pin "5") (pinfunction "5_5") (pintype "bidirectional"))
      (node (ref "U$14") (pin "6") (pinfunction "6_6") (pintype "bidirectional"))
      (node (ref "U$14") (pin "D") (pinfunction "D0_D") (pintype "bidirectional"))
    )
    (net (code "45") (name "RX_NXTN") (class "Default")
      (node (ref "U1") (pin "8") (pinfunction "TX2_8") (pintype "bidirectional"))
      (node (ref "X2") (pin "P$2") (pinfunction "2_P$2") (pintype "passive"))
    )
    (net (code "46") (name "TS_LED_OUT") (class "Default")
      (node (ref "R17") (pin "2") (pinfunction "2_2") (pintype "passive"))
      (node (ref "X8") (pin "P$1") (pinfunction "1_P$1") (pintype "passive"))
    )
    (net (code "47") (name "TS_OFF") (class "Default")
      (node (ref "R17") (pin "1") (pinfunction "1_1") (pintype "passive"))
      (node (ref "X3") (pin "P$1") (pinfunction "1_P$1") (pintype "passive"))
    )
    (net (code "48") (name "TX_NXTN") (class "Default")
      (node (ref "U1") (pin "7") (pinfunction "RX2_7") (pintype "bidirectional"))
      (node (ref "X2") (pin "P$1") (pinfunction "1_P$1") (pintype "passive"))
    )
    (net (code "49") (name "unconnected-(U1-A0-Pad14)") (class "Default")
      (node (ref "U1") (pin "14") (pinfunction "A0_14") (pintype "bidirectional"))
    )
    (net (code "50") (name "unconnected-(U1-A3-Pad17)") (class "Default")
      (node (ref "U1") (pin "17") (pinfunction "A3_17") (pintype "bidirectional"))
    )
    (net (code "51") (name "unconnected-(U1-A7-Pad21)") (class "Default")
      (node (ref "U1") (pin "21") (pinfunction "A7_21") (pintype "bidirectional"))
    )
    (net (code "52") (name "unconnected-(U1-A8-Pad22)") (class "Default")
      (node (ref "U1") (pin "22") (pinfunction "A8_22") (pintype "bidirectional"))
    )
    (net (code "53") (name "unconnected-(U1-A9-Pad23)") (class "Default")
      (node (ref "U1") (pin "23") (pinfunction "A9_23") (pintype "bidirectional"))
    )
    (net (code "54") (name "unconnected-(U1-A10-Pad24)") (class "Default")
      (node (ref "U1") (pin "24") (pinfunction "A10_24") (pintype "bidirectional"))
    )
    (net (code "55") (name "unconnected-(U1-A11-Pad25)") (class "Default")
      (node (ref "U1") (pin "25") (pinfunction "A11_25") (pintype "bidirectional"))
    )
    (net (code "56") (name "unconnected-(U1-A12-Pad26)") (class "Default")
      (node (ref "U1") (pin "26") (pinfunction "A12_26") (pintype "bidirectional"))
    )
    (net (code "57") (name "unconnected-(U1-A13-Pad27)") (class "Default")
      (node (ref "U1") (pin "27") (pinfunction "A13_27") (pintype "bidirectional"))
    )
    (net (code "58") (name "unconnected-(U1-A14-Pad38)") (class "Default")
      (node (ref "U1") (pin "38") (pinfunction "A14_38") (pintype "bidirectional"))
    )
    (net (code "59") (name "unconnected-(U1-A15-Pad39)") (class "Default")
      (node (ref "U1") (pin "39") (pinfunction "A15_39") (pintype "bidirectional"))
    )
    (net (code "60") (name "unconnected-(U1-A16-Pad40)") (class "Default")
      (node (ref "U1") (pin "40") (pinfunction "A16_40") (pintype "bidirectional"))
    )
    (net (code "61") (name "unconnected-(U1-A17-Pad41)") (class "Default")
      (node (ref "U1") (pin "41") (pinfunction "A17_41") (pintype "bidirectional"))
    )
    (net (code "62") (name "unconnected-(U1-BCLK2-Pad4)") (class "Default")
      (node (ref "U1") (pin "4") (pinfunction "BCLK2_4") (pintype "bidirectional"))
    )
    (net (code "63") (name "unconnected-(U1-CS1-Pad10)") (class "Default")
      (node (ref "U1") (pin "10") (pinfunction "CS1_10") (pintype "bidirectional"))
    )
    (net (code "64") (name "unconnected-(U1-CS2-Pad36)") (class "Default")
      (node (ref "U1") (pin "36") (pinfunction "CS2_36") (pintype "bidirectional"))
    )
    (net (code "65") (name "unconnected-(U1-CS3-Pad37)") (class "Default")
      (node (ref "U1") (pin "37") (pinfunction "CS3_37") (pintype "bidirectional"))
    )
    (net (code "66") (name "unconnected-(U1-IN2-Pad5)") (class "Default")
      (node (ref "U1") (pin "5") (pinfunction "IN2_5") (pintype "bidirectional"))
    )
    (net (code "67") (name "unconnected-(U1-LRCLK2-Pad3)") (class "Default")
      (node (ref "U1") (pin "3") (pinfunction "LRCLK2_3") (pintype "bidirectional"))
    )
    (net (code "68") (name "unconnected-(U1-MCLK2-Pad33)") (class "Default")
      (node (ref "U1") (pin "33") (pinfunction "MCLK2_33") (pintype "bidirectional"))
    )
    (net (code "69") (name "unconnected-(U1-MISO-Pad12)") (class "Default")
      (node (ref "U1") (pin "12") (pinfunction "MISO_12") (pintype "bidirectional"))
    )
    (net (code "70") (name "unconnected-(U1-MOSI-Pad11)") (class "Default")
      (node (ref "U1") (pin "11") (pinfunction "MOSI_11") (pintype "bidirectional"))
    )
    (net (code "71") (name "unconnected-(U1-OUT1B-Pad32)") (class "Default")
      (node (ref "U1") (pin "32") (pinfunction "OUT1B_32") (pintype "output"))
    )
    (net (code "72") (name "unconnected-(U1-OUT1C-Pad9)") (class "Default")
      (node (ref "U1") (pin "9") (pinfunction "OUT1C_9") (pintype "output"))
    )
    (net (code "73") (name "unconnected-(U1-OUT1D-Pad6)") (class "Default")
      (node (ref "U1") (pin "6") (pinfunction "OUT1D_6") (pintype "output"))
    )
    (net (code "74") (name "unconnected-(U1-OUT2-Pad2)") (class "Default")
      (node (ref "U1") (pin "2") (pinfunction "OUT2_2") (pintype "output"))
    )
    (net (code "75") (name "unconnected-(U1-PadD+)") (class "Default")
      (node (ref "U1") (pin "D+") (pinfunction "D+_D+") (pintype "bidirectional"))
    )
    (net (code "76") (name "unconnected-(U1-PadD-)") (class "Default")
      (node (ref "U1") (pin "D-") (pinfunction "D-_D-") (pintype "bidirectional"))
    )
    (net (code "77") (name "unconnected-(U1-PadLED)") (class "Default")
      (node (ref "U1") (pin "LED") (pinfunction "LED_LED") (pintype "bidirectional"))
    )
    (net (code "78") (name "unconnected-(U1-PadON{slash}OFF)") (class "Default")
      (node (ref "U1") (pin "ON/OFF") (pinfunction "ON/OFF_ON/OFF") (pintype "bidirectional"))
    )
    (net (code "79") (name "unconnected-(U1-PadPROGRAM)") (class "Default")
      (node (ref "U1") (pin "PROGRAM") (pinfunction "PROGRAM_PROGRAM") (pintype "bidirectional"))
    )
    (net (code "80") (name "unconnected-(U1-PadR+)") (class "Default")
      (node (ref "U1") (pin "R+") (pinfunction "R+_R+") (pintype "bidirectional"))
    )
    (net (code "81") (name "unconnected-(U1-PadR-)") (class "Default")
      (node (ref "U1") (pin "R-") (pinfunction "R-_R-") (pintype "bidirectional"))
    )
    (net (code "82") (name "unconnected-(U1-PadT+)") (class "Default")
      (node (ref "U1") (pin "T+") (pinfunction "T+_T+") (pintype "bidirectional"))
    )
    (net (code "83") (name "unconnected-(U1-PadT-)") (class "Default")
      (node (ref "U1") (pin "T-") (pinfunction "T-_T-") (pintype "bidirectional"))
    )
    (net (code "84") (name "unconnected-(U1-PadVBAT)") (class "Default")
      (node (ref "U1") (pin "VBAT") (pinfunction "VBAT_VBAT") (pintype "passive"))
    )
    (net (code "85") (name "unconnected-(U1-PadVUSB)") (class "Default")
      (node (ref "U1") (pin "VUSB") (pinfunction "VUSB_VUSB") (pintype "passive"))
    )
    (net (code "86") (name "unconnected-(U1-RX7-Pad28)") (class "Default")
      (node (ref "U1") (pin "28") (pinfunction "RX7_28") (pintype "bidirectional"))
    )
    (net (code "87") (name "unconnected-(U1-SCK-Pad13)") (class "Default")
      (node (ref "U1") (pin "13") (pinfunction "SCK_13") (pintype "bidirectional"))
    )
    (net (code "88") (name "unconnected-(U1-TX7-Pad29)") (class "Default")
      (node (ref "U1") (pin "29") (pinfunction "TX7_29") (pintype "bidirectional"))
    )
    (net (code "89") (name "unconnected-(U2-Pad1)") (class "Default")
      (node (ref "U2") (pin "1") (pinfunction "1_1") (pintype "bidirectional"))
    )
    (net (code "90") (name "unconnected-(U2-Pad2)") (class "Default")
      (node (ref "U2") (pin "2") (pinfunction "2_2") (pintype "bidirectional"))
    )
    (net (code "91") (name "unconnected-(X1-2-PadP$2)") (class "Default")
      (node (ref "X1") (pin "P$2") (pinfunction "2_P$2") (pintype "passive"))
    )
  )
)
